# PWR_3V3.net
KiCad netlist of a schematic drawn in Altium Designer
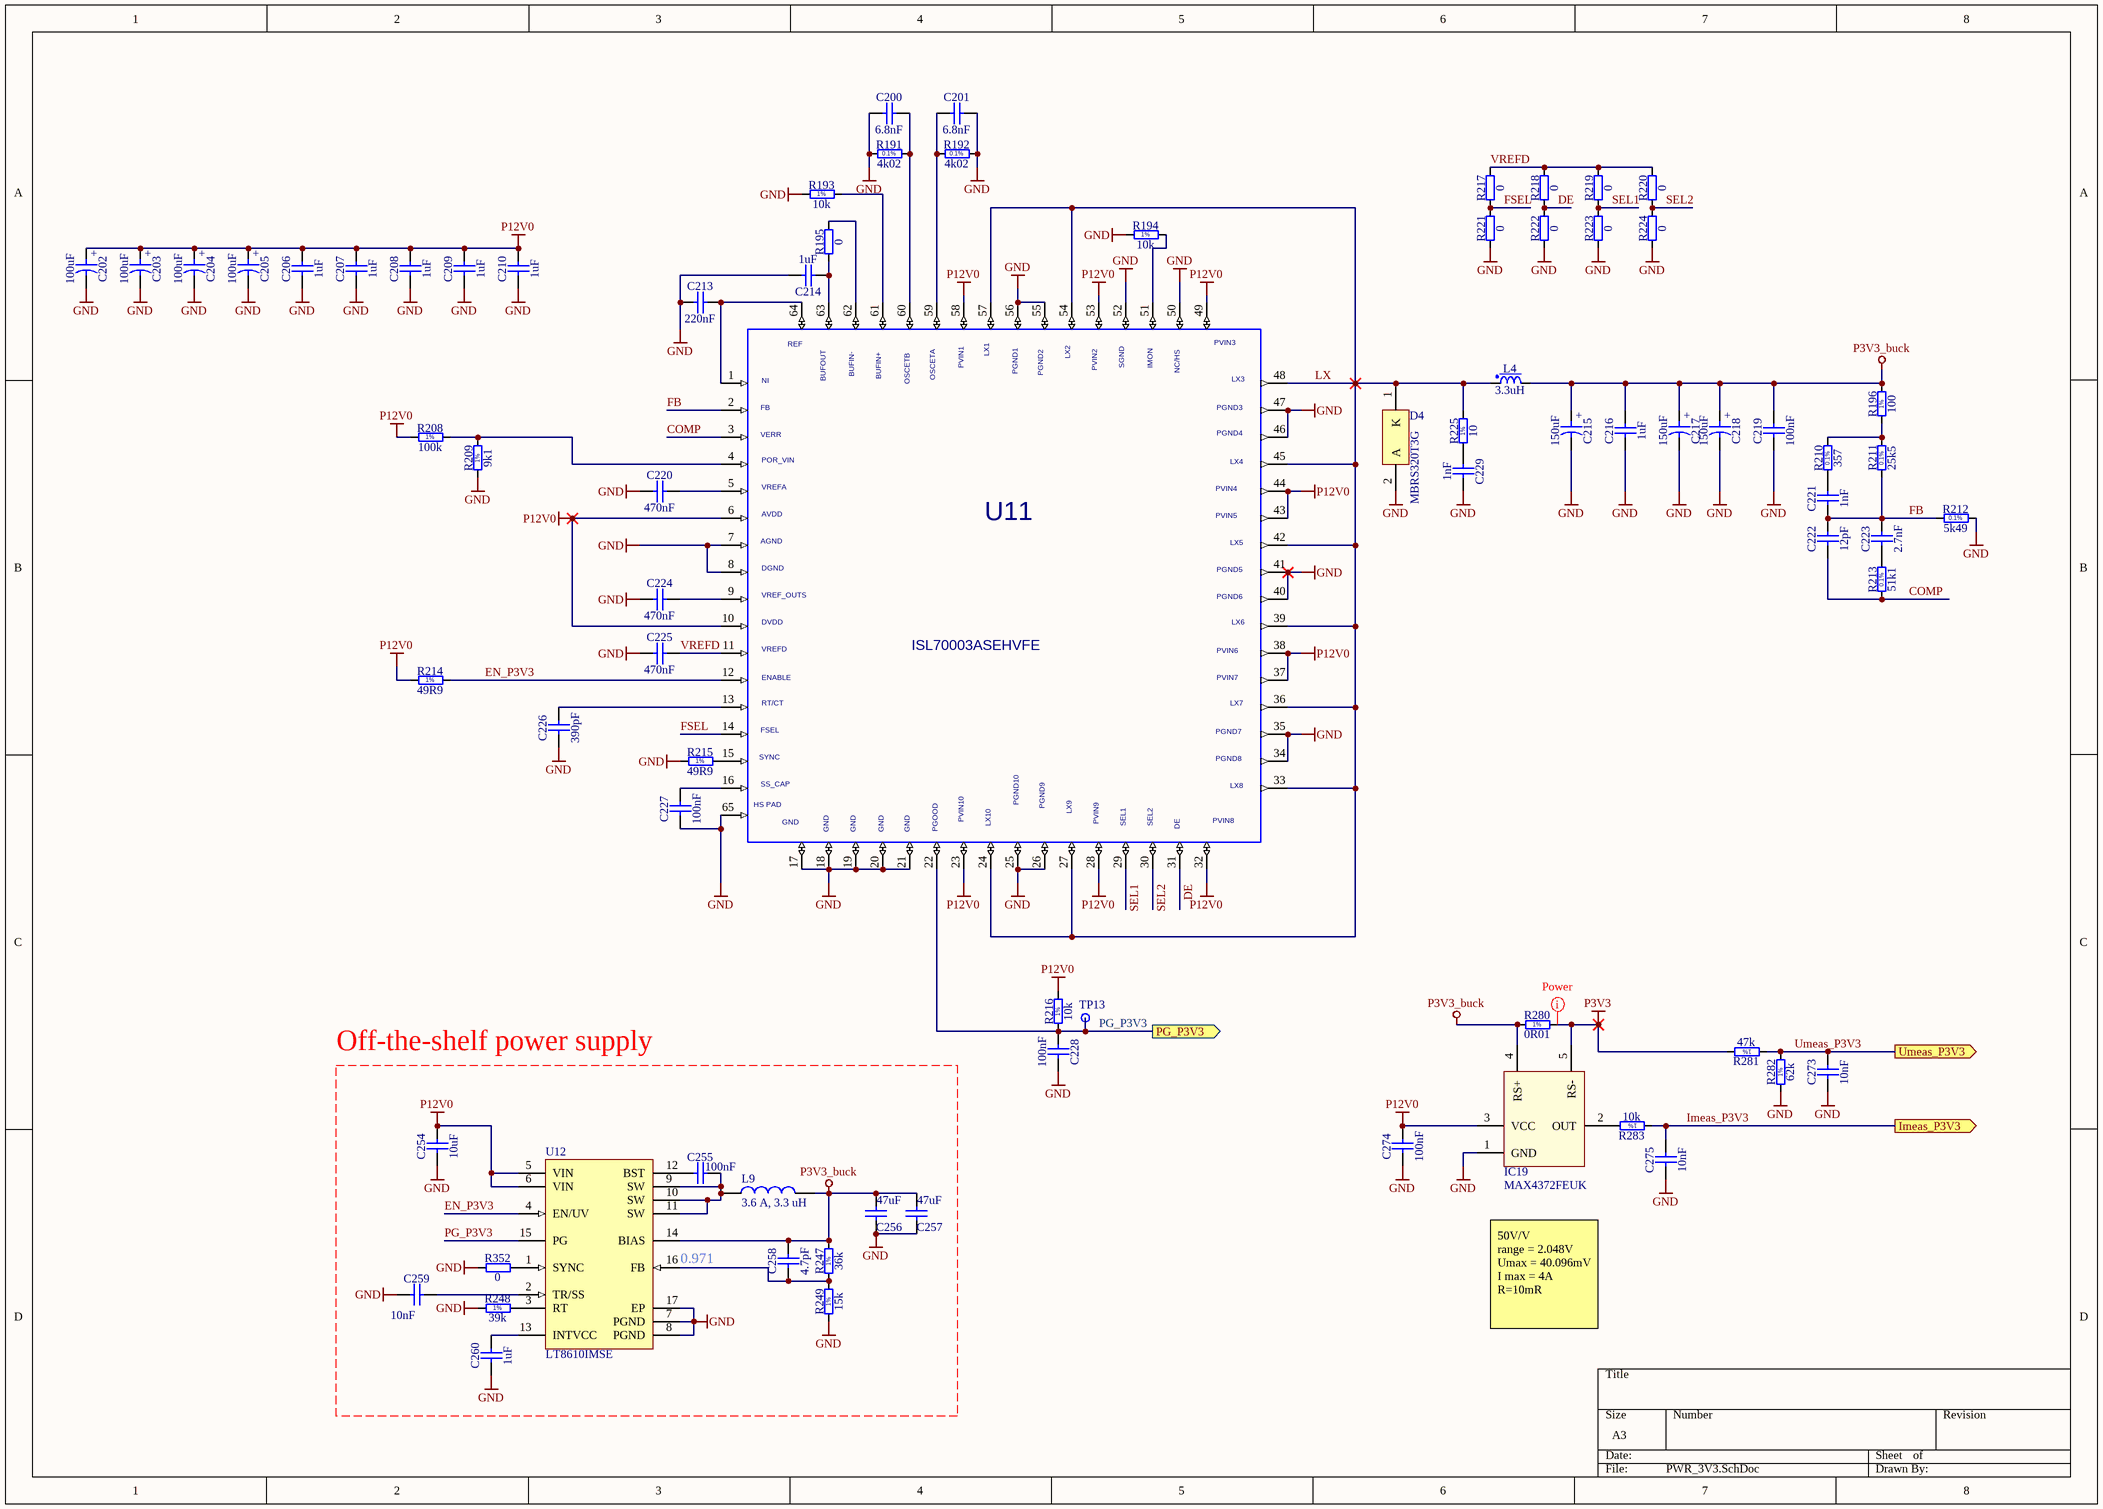
[diagram p0: PWR_3V3.SchDoc]

(export (version "E")
  (design (tool "Eeschema 10.0.6"))
  (components
    (comp (ref "C200")
      (value "6.8nF")
      (footprint "CAPC1005X55N")
      (description "Non-polarised capacitor")
      (fields
        (field (name "PART NUMBER") "CC0402_6.8NF_16V_10%_X7R")
        (field (name "VOLTAGE") "16V")
        (field (name "AUTHOR") "CERN DEM JLC")
      )
      (libsource (lib "Capacitors") (part "Capacitor - non polarized"))
    )
    (comp (ref "C201")
      (value "6.8nF")
      (footprint "CAPC1005X55N")
      (description "Non-polarised capacitor")
      (fields
        (field (name "PART NUMBER") "CC0402_6.8NF_16V_10%_X7R")
        (field (name "VOLTAGE") "16V")
        (field (name "AUTHOR") "CERN DEM JLC")
      )
      (libsource (lib "Capacitors") (part "Capacitor - non polarized"))
    )
    (comp (ref "C202")
      (value "100uF")
      (footprint "CAPMP7343X430N")
      (description "Polarised capacitor")
      (fields
        (field (name "PART NUMBER") "CTE7343-43_100UF_25V_10%_LESR0150")
        (field (name "VOLTAGE") "25V")
        (field (name "AUTHOR") "CERN DEM JLC")
      )
      (libsource (lib "Capacitors") (part "Capacitor - polarized"))
    )
    (comp (ref "C203")
      (value "100uF")
      (footprint "CAPMP7343X430N")
      (description "Polarised capacitor")
      (fields
        (field (name "PART NUMBER") "CTE7343-43_100UF_25V_10%_LESR0150")
        (field (name "VOLTAGE") "25V")
        (field (name "AUTHOR") "CERN DEM JLC")
      )
      (libsource (lib "Capacitors") (part "Capacitor - polarized"))
    )
    (comp (ref "C204")
      (value "100uF")
      (footprint "CAPMP7343X430N")
      (description "Polarised capacitor")
      (fields
        (field (name "PART NUMBER") "CTE7343-43_100UF_25V_10%_LESR0150")
        (field (name "VOLTAGE") "25V")
        (field (name "AUTHOR") "CERN DEM JLC")
      )
      (libsource (lib "Capacitors") (part "Capacitor - polarized"))
    )
    (comp (ref "C205")
      (value "100uF")
      (footprint "CAPMP7343X430N")
      (description "Polarised capacitor")
      (fields
        (field (name "PART NUMBER") "CTE7343-43_100UF_25V_10%_LESR0150")
        (field (name "VOLTAGE") "25V")
        (field (name "AUTHOR") "CERN DEM JLC")
      )
      (libsource (lib "Capacitors") (part "Capacitor - polarized"))
    )
    (comp (ref "C206")
      (value "1uF")
      (footprint "CAPC5650X165N")
      (description "Non-polarised capacitor")
      (fields
        (field (name "PART NUMBER") "CC2220_1UF_200V_10%_X7R")
        (field (name "VOLTAGE") "200V")
        (field (name "AUTHOR") "CERN DEM JLC")
      )
      (libsource (lib "Capacitors") (part "Capacitor - non polarized"))
    )
    (comp (ref "C207")
      (value "1uF")
      (footprint "CAPC5650X165N")
      (description "Non-polarised capacitor")
      (fields
        (field (name "PART NUMBER") "CC2220_1UF_200V_10%_X7R")
        (field (name "VOLTAGE") "200V")
        (field (name "AUTHOR") "CERN DEM JLC")
      )
      (libsource (lib "Capacitors") (part "Capacitor - non polarized"))
    )
    (comp (ref "C208")
      (value "1uF")
      (footprint "CAPC5650X165N")
      (description "Non-polarised capacitor")
      (fields
        (field (name "PART NUMBER") "CC2220_1UF_200V_10%_X7R")
        (field (name "VOLTAGE") "200V")
        (field (name "AUTHOR") "CERN DEM JLC")
      )
      (libsource (lib "Capacitors") (part "Capacitor - non polarized"))
    )
    (comp (ref "C209")
      (value "1uF")
      (footprint "CAPC5650X165N")
      (description "Non-polarised capacitor")
      (fields
        (field (name "PART NUMBER") "CC2220_1UF_200V_10%_X7R")
        (field (name "VOLTAGE") "200V")
        (field (name "AUTHOR") "CERN DEM JLC")
      )
      (libsource (lib "Capacitors") (part "Capacitor - non polarized"))
    )
    (comp (ref "C210")
      (value "1uF")
      (footprint "CAPC5650X165N")
      (description "Non-polarised capacitor")
      (fields
        (field (name "PART NUMBER") "CC2220_1UF_200V_10%_X7R")
        (field (name "VOLTAGE") "200V")
        (field (name "AUTHOR") "CERN DEM JLC")
      )
      (libsource (lib "Capacitors") (part "Capacitor - non polarized"))
    )
    (comp (ref "C213")
      (value "220nF")
      (footprint "CAPC1005X55N")
      (description "Non-polarised capacitor")
      (fields
        (field (name "PART NUMBER") "CC0402_220NF_16V_10%_X7R")
        (field (name "VOLTAGE") "16V")
        (field (name "AUTHOR") "CERN DEM JLC")
      )
      (libsource (lib "Capacitors") (part "Capacitor - non polarized"))
    )
    (comp (ref "C214")
      (value "1uF")
      (footprint "CAPC1005X55N")
      (description "Non-polarised capacitor")
      (fields
        (field (name "PART NUMBER") "CC0402_1UF_16V_10%_X5R")
        (field (name "VOLTAGE") "16V")
        (field (name "AUTHOR") "CERN DEM JLC")
      )
      (libsource (lib "Capacitors") (part "Capacitor - non polarized"))
    )
    (comp (ref "C215")
      (value "150uF")
      (footprint "CAPMP6032X280N")
      (description "Polarised capacitor")
      (fields
        (field (name "PART NUMBER") "CTE6032-28_150UF_10V_10%")
        (field (name "VOLTAGE") "10V")
        (field (name "AUTHOR") "CERN DEM JLC")
      )
      (libsource (lib "Capacitors") (part "Capacitor - polarized"))
    )
    (comp (ref "C216")
      (value "1uF")
      (footprint "CAPC5650X165N")
      (description "Non-polarised capacitor")
      (fields
        (field (name "PART NUMBER") "CC2220_1UF_200V_10%_X7R")
        (field (name "VOLTAGE") "200V")
        (field (name "AUTHOR") "CERN DEM JLC")
      )
      (libsource (lib "Capacitors") (part "Capacitor - non polarized"))
    )
    (comp (ref "C217")
      (value "150uF")
      (footprint "CAPMP6032X280N")
      (description "Polarised capacitor")
      (fields
        (field (name "PART NUMBER") "CTE6032-28_150UF_10V_10%")
        (field (name "VOLTAGE") "10V")
        (field (name "AUTHOR") "CERN DEM JLC")
      )
      (libsource (lib "Capacitors") (part "Capacitor - polarized"))
    )
    (comp (ref "C218")
      (value "150uF")
      (footprint "CAPMP6032X280N")
      (description "Polarised capacitor")
      (fields
        (field (name "PART NUMBER") "CTE6032-28_150UF_10V_10%")
        (field (name "VOLTAGE") "10V")
        (field (name "AUTHOR") "CERN DEM JLC")
      )
      (libsource (lib "Capacitors") (part "Capacitor - polarized"))
    )
    (comp (ref "C219")
      (value "100nF")
      (footprint "CAPC1608X87N")
      (description "Non-polarised capacitor")
      (fields
        (field (name "PART NUMBER") "CC0603_100NF_50V_10%_X5R")
        (field (name "VOLTAGE") "50V")
        (field (name "AUTHOR") "CERN DEM MR")
      )
      (libsource (lib "Capacitors") (part "Capacitor - non polarized"))
    )
    (comp (ref "C220")
      (value "470nF")
      (footprint "CAPC1005X55N")
      (description "Non-polarised capacitor")
      (fields
        (field (name "PART NUMBER") "CC0402_470NF_16V_10%_X5R")
        (field (name "VOLTAGE") "16V")
        (field (name "AUTHOR") "CERN DEM JLC")
      )
      (libsource (lib "Capacitors") (part "Capacitor - non polarized"))
    )
    (comp (ref "C221")
      (value "1nF")
      (footprint "CAPC1005X55N")
      (description "Non-polarised capacitor")
      (fields
        (field (name "PART NUMBER") "CC0402_1NF_50V_10%_X7R")
        (field (name "VOLTAGE") "50V")
        (field (name "AUTHOR") "CERN DEM JLC")
      )
      (libsource (lib "Capacitors") (part "Capacitor - non polarized"))
    )
    (comp (ref "C222")
      (value "12pF")
      (footprint "CAPC1005X55N")
      (description "Non-polarised capacitor")
      (fields
        (field (name "PART NUMBER") "CC0402_12PF_50V_5%_C0G")
        (field (name "VOLTAGE") "50V")
        (field (name "AUTHOR") "CERN DEM JLC")
      )
      (libsource (lib "Capacitors") (part "Capacitor - non polarized"))
    )
    (comp (ref "C223")
      (value "2.7nF")
      (footprint "CAPC1005X55N")
      (description "Non-polarised capacitor")
      (fields
        (field (name "PART NUMBER") "CC0402_2.7NF_50V_10%_X7R")
        (field (name "VOLTAGE") "50V")
        (field (name "AUTHOR") "CERN DEM JLC")
      )
      (libsource (lib "Capacitors") (part "Capacitor - non polarized"))
    )
    (comp (ref "C224")
      (value "470nF")
      (footprint "CAPC1005X55N")
      (description "Non-polarised capacitor")
      (fields
        (field (name "PART NUMBER") "CC0402_470NF_16V_10%_X5R")
        (field (name "VOLTAGE") "16V")
        (field (name "AUTHOR") "CERN DEM JLC")
      )
      (libsource (lib "Capacitors") (part "Capacitor - non polarized"))
    )
    (comp (ref "C225")
      (value "470nF")
      (footprint "CAPC1005X55N")
      (description "Non-polarised capacitor")
      (fields
        (field (name "PART NUMBER") "CC0402_470NF_16V_10%_X5R")
        (field (name "VOLTAGE") "16V")
        (field (name "AUTHOR") "CERN DEM JLC")
      )
      (libsource (lib "Capacitors") (part "Capacitor - non polarized"))
    )
    (comp (ref "C226")
      (value "390pF")
      (footprint "CAPC1608X87N")
      (description "Non-polarised capacitor")
      (fields
        (field (name "PART NUMBER") "CC0603_390PF_50V_5%_NP0")
        (field (name "VOLTAGE") "50V")
        (field (name "AUTHOR") "CERN DEM JLC")
      )
      (libsource (lib "Capacitors") (part "Capacitor - non polarized"))
    )
    (comp (ref "C227")
      (value "100nF")
      (footprint "CAPC1005X55N")
      (description "Non-polarised capacitor")
      (fields
        (field (name "PART NUMBER") "CC0402_100NF_16V_10%_X5R")
        (field (name "VOLTAGE") "16V")
        (field (name "AUTHOR") "CERN DEM JLC")
      )
      (libsource (lib "Capacitors") (part "Capacitor - non polarized"))
    )
    (comp (ref "C228")
      (value "100nF")
      (footprint "CAPC1005X55N")
      (description "Non-polarised capacitor")
      (fields
        (field (name "PART NUMBER") "CC0402_100NF_16V_10%_X5R")
        (field (name "VOLTAGE") "16V")
        (field (name "AUTHOR") "CERN DEM JLC")
      )
      (libsource (lib "Capacitors") (part "Capacitor - non polarized"))
    )
    (comp (ref "C229")
      (value "1nF")
      (footprint "CAPC1608X90N")
      (description "Non-polarised capacitor")
      (fields
        (field (name "PART NUMBER") "CC0603_1NF_50V_1%_NP0")
        (field (name "VOLTAGE") "50V")
        (field (name "AUTHOR") "CERN DEM JLC")
      )
      (libsource (lib "Capacitors") (part "Capacitor - non polarized"))
    )
    (comp (ref "C254")
      (value "10uF")
      (footprint "CAPC2012X95N")
      (description "Non-polarised capacitor")
      (fields
        (field (name "PART NUMBER") "CC0805_10UF_25V_10%_X5R")
        (field (name "VOLTAGE") "25V")
        (field (name "AUTHOR") "CERN DEM JLC")
      )
      (libsource (lib "Capacitors") (part "Capacitor - non polarized"))
    )
    (comp (ref "C255")
      (value "100nF")
      (footprint "CAPC1005X55N")
      (description "Non-polarised capacitor")
      (fields
        (field (name "PART NUMBER") "CC0402_100NF_25V_10%_X7R_YUDEN_TMK105B7104KVHF")
        (field (name "VOLTAGE") "25V")
        (field (name "AUTHOR") "CERN DEM JLC")
      )
      (libsource (lib "Capacitors") (part "Capacitor - non polarized"))
    )
    (comp (ref "C256")
      (value "47uF")
      (footprint "CAPC2012X140N")
      (description "Non-polarised capacitor")
      (fields
        (field (name "PART NUMBER") "CC0805_47UF_6.3V_20%_X5R")
        (field (name "MANUFACTURER") "GENERIC")
        (field (name "AUTHOR") "CERN DEM JLC")
      )
      (libsource (lib "Capacitors") (part "Capacitor - non polarized"))
    )
    (comp (ref "C257")
      (value "47uF")
      (footprint "CAPC2012X140N")
      (description "Non-polarised capacitor")
      (fields
        (field (name "PART NUMBER") "CC0805_47UF_6.3V_20%_X5R")
        (field (name "MANUFACTURER") "GENERIC")
        (field (name "AUTHOR") "CERN DEM JLC")
      )
      (libsource (lib "Capacitors") (part "Capacitor - non polarized"))
    )
    (comp (ref "C258")
      (value "4.7pF")
      (footprint "CAPC1005X55N")
      (description "Non-polarised capacitor")
      (fields
        (field (name "PART NUMBER") "CC0402_4.7PF_50V_0.25PF_C0G")
        (field (name "VOLTAGE") "50V")
        (field (name "AUTHOR") "CERN DEM JLC")
      )
      (libsource (lib "Capacitors") (part "Capacitor - non polarized"))
    )
    (comp (ref "C259")
      (value "10nF")
      (footprint "CAPC1005X55N")
      (description "Non-polarised capacitor")
      (fields
        (field (name "PART NUMBER") "CC0402_10NF_25V_10%_X7R")
        (field (name "VOLTAGE") "25V")
        (field (name "AUTHOR") "CERN DEM JLC")
      )
      (libsource (lib "Capacitors") (part "Capacitor - non polarized"))
    )
    (comp (ref "C260")
      (value "1uF")
      (footprint "CAPC1608X87N")
      (description "Non-polarised capacitor")
      (fields
        (field (name "PART NUMBER") "CC0603_1UF_25V_10%_X7R")
        (field (name "VOLTAGE") "25V")
        (field (name "AUTHOR") "CERN DEM JLC")
      )
      (libsource (lib "Capacitors") (part "Capacitor - non polarized"))
    )
    (comp (ref "C273")
      (value "10nF")
      (footprint "CAPC1005X55N")
      (description "Non-polarised capacitor")
      (fields
        (field (name "PART NUMBER") "CC0402_10NF_50V_10%_X7R")
        (field (name "VOLTAGE") "50V")
        (field (name "AUTHOR") "CERN DEM MR")
      )
      (libsource (lib "Capacitors") (part "Capacitor - non polarized"))
    )
    (comp (ref "C274")
      (value "100nF")
      (footprint "CAPC1005X55N")
      (description "Non-polarised capacitor")
      (fields
        (field (name "PART NUMBER") "CC0402_100NF_25V_10%_X7R_YUDEN_TMK105B7104KVHF")
        (field (name "VOLTAGE") "25V")
        (field (name "AUTHOR") "CERN DEM JLC")
      )
      (libsource (lib "Capacitors") (part "Capacitor - non polarized"))
    )
    (comp (ref "C275")
      (value "10nF")
      (footprint "CAPC1005X55N")
      (description "Non-polarised capacitor")
      (fields
        (field (name "PART NUMBER") "CC0402_10NF_50V_10%_X7R")
        (field (name "VOLTAGE") "50V")
        (field (name "AUTHOR") "CERN DEM MR")
      )
      (libsource (lib "Capacitors") (part "Capacitor - non polarized"))
    )
    (comp (ref "D4")
      (value "MBRS320T3G")
      (footprint "ONSC-SMC-2-403-03_V")
      (description "Schottky Power Rectifier, 2-Pin SMC, Pb-Free, Tape and Reel")
      (fields (field (name "MANUFACTURER") "On Semiconductor"))
      (libsource (lib "Altium Content Vault") (part "ONSC-D-K1A2-2_A"))
    )
    (comp (ref "IC19")
      (value "MAX4372FEUK")
      (footprint "SOT95P270X145-5N")
      (fields (field (name "MANUFACTURER") "Maxim"))
      (libsource (lib "LIBRARY_SCH") (part "PM_MAX4372FEUK"))
    )
    (comp (ref "L4")
      (value "3.3uH")
      (footprint "IND_LAIRD_MGV10043R3M-10")
      (description "Inductor With Magnetic core 1Dot")
      (fields
        (field (name "PART NUMBER") "IND_3.3UH_20%_LAIRD_MGV10043R3M-10")
        (field (name "POWER") "10A")
        (field (name "AUTHOR") "CERN DEM BC")
      )
      (libsource (lib "Inductors & Transformers") (part "Inductor With Magnetic core 1Dot"))
    )
    (comp (ref "L9")
      (value "3.6 A, 3.3 uH")
      (footprint "WE-MAIA_4020")
      (description "WE-MAIA SMD Power Inductor, size 4020, 3.6 A, 3.3 uH")
      (fields (field (name "PART NUMBER") "78438356033") (field (name "PUBLISHER") "Wurth Elektronik"))
      (libsource (lib "ALTIUM-WE-MAIA-rev17b") (part "78438356033"))
    )
    (comp (ref "R191")
      (value "4k02")
      (footprint "RESC1608X55N")
      (description "Resistor - 0.1%")
      (fields
        (field (name "PART NUMBER") "R0603_4K02_0.1%_0.063W_10PPM")
        (field (name "POWER") "0.063W")
        (field (name "AUTHOR") "CERN DEM JLC")
      )
      (libsource (lib "Resistors") (part "Resistor - 0.1%"))
    )
    (comp (ref "R192")
      (value "4k02")
      (footprint "RESC1608X55N")
      (description "Resistor - 0.1%")
      (fields
        (field (name "PART NUMBER") "R0603_4K02_0.1%_0.063W_10PPM")
        (field (name "POWER") "0.063W")
        (field (name "AUTHOR") "CERN DEM JLC")
      )
      (libsource (lib "Resistors") (part "Resistor - 0.1%"))
    )
    (comp (ref "R193")
      (value "10k")
      (footprint "RESC1005X40N")
      (description "Resistor - 1%")
      (fields
        (field (name "PART NUMBER") "R0402_10K_1%_0.0625W_100PPM")
        (field (name "POWER") "0.0625W")
        (field (name "AUTHOR") "CERN DEM JLC")
      )
      (libsource (lib "Resistors") (part "Resistor - 1%"))
    )
    (comp (ref "R194")
      (value "10k")
      (footprint "RESC1005X40N")
      (description "Resistor - 1%")
      (fields
        (field (name "PART NUMBER") "R0402_10K_1%_0.0625W_100PPM")
        (field (name "POWER") "0.0625W")
        (field (name "AUTHOR") "CERN DEM JLC")
      )
      (libsource (lib "Resistors") (part "Resistor - 1%"))
    )
    (comp (ref "R195")
      (value "0")
      (footprint "RESC1005X40N")
      (description "Resistor")
      (fields
        (field (name "PART NUMBER") "R0402_0R_JUMPER")
        (field (name "MANUFACTURER") "GENERIC")
        (field (name "AUTHOR") "CERN DEM JLC")
      )
      (libsource (lib "Resistors") (part "Resistor"))
    )
    (comp (ref "R196")
      (value "100")
      (footprint "RESC1005X40N")
      (description "Resistor - 1%")
      (fields
        (field (name "PART NUMBER") "R0402_100R_1%_0.0625W_100PPM")
        (field (name "POWER") "0.0625W")
        (field (name "AUTHOR") "CERN DEM JLC")
      )
      (libsource (lib "Resistors") (part "Resistor - 1%"))
    )
    (comp (ref "R208")
      (value "100k")
      (footprint "RESC1005X40N")
      (description "Resistor - 1%")
      (fields
        (field (name "PART NUMBER") "R0402_100K_1%_0.0625W_100PPM")
        (field (name "POWER") "0.0625W")
        (field (name "AUTHOR") "CERN DEM JLC")
      )
      (libsource (lib "Resistors") (part "Resistor - 1%"))
    )
    (comp (ref "R209")
      (value "9k1")
      (footprint "RESC1005X40N")
      (description "Resistor - 1%")
      (fields
        (field (name "PART NUMBER") "R0402_9K1_1%_0.0625W_100PPM")
        (field (name "POWER") "0.0625W")
        (field (name "AUTHOR") "CERN DEM JLC")
      )
      (libsource (lib "Resistors") (part "Resistor - 1%"))
    )
    (comp (ref "R210")
      (value "357")
      (footprint "RESC1608X55N")
      (description "Resistor - 0.1%")
      (fields
        (field (name "PART NUMBER") "R0603_357R_0.1%_0.063W_10PPM")
        (field (name "POWER") "0.063W")
        (field (name "AUTHOR") "CERN DEM JLC")
      )
      (libsource (lib "Resistors") (part "Resistor - 0.1%"))
    )
    (comp (ref "R211")
      (value "25k5")
      (footprint "RESC1608X55N")
      (description "Resistor - 0.1%")
      (fields
        (field (name "PART NUMBER") "R0603_25K5_0.1%_0.063W_10PPM")
        (field (name "POWER") "0.063W")
        (field (name "AUTHOR") "CERN DEM JLC")
      )
      (libsource (lib "Resistors") (part "Resistor - 0.1%"))
    )
    (comp (ref "R212")
      (value "5k49")
      (footprint "RESC1608X55N")
      (description "Resistor - 0.1%")
      (fields
        (field (name "PART NUMBER") "R0603_5K49_0.1%_0.063W_10PPM")
        (field (name "POWER") "0.063W")
        (field (name "AUTHOR") "CERN DEM JLC")
      )
      (libsource (lib "Resistors") (part "Resistor - 0.1%"))
    )
    (comp (ref "R213")
      (value "51k1")
      (footprint "RESC1608X55N")
      (description "Resistor - 0.1%")
      (fields
        (field (name "PART NUMBER") "R0603_51K1_0.1%_0.063W_10PPM")
        (field (name "POWER") "0.063W")
        (field (name "AUTHOR") "CERN DEM JLC")
      )
      (libsource (lib "Resistors") (part "Resistor - 0.1%"))
    )
    (comp (ref "R214")
      (value "49R9")
      (footprint "RESC1608X55N")
      (description "Resistor - 1%")
      (fields
        (field (name "PART NUMBER") "R0603_49K9_1%_0.1W_100PPM")
        (field (name "POWER") "0.1W")
        (field (name "AUTHOR") "CERN DEM JLC")
      )
      (libsource (lib "Resistors") (part "Resistor - 1%"))
    )
    (comp (ref "R215")
      (value "49R9")
      (footprint "RESC1005X40N")
      (description "Resistor - 1%")
      (fields
        (field (name "PART NUMBER") "R0402_49R9_1%_0.0625W_100PPM")
        (field (name "POWER") "0.0625W")
        (field (name "AUTHOR") "CERN DEM JLC")
      )
      (libsource (lib "Resistors") (part "Resistor - 1%"))
    )
    (comp (ref "R216")
      (value "10k")
      (footprint "RESC1005X40N")
      (description "Resistor - 1%")
      (fields
        (field (name "PART NUMBER") "R0402_10K_1%_0.0625W_100PPM")
        (field (name "POWER") "0.0625W")
        (field (name "AUTHOR") "CERN DEM JLC")
      )
      (libsource (lib "Resistors") (part "Resistor - 1%"))
    )
    (comp (ref "R217")
      (value "0")
      (footprint "RESC1005X40N")
      (description "Resistor")
      (fields
        (field (name "PART NUMBER") "R0402_0R_JUMPER")
        (field (name "MANUFACTURER") "GENERIC")
        (field (name "AUTHOR") "CERN DEM JLC")
      )
      (libsource (lib "Resistors") (part "Resistor"))
    )
    (comp (ref "R218")
      (value "0")
      (footprint "RESC1005X40N")
      (description "Resistor")
      (fields
        (field (name "PART NUMBER") "R0402_0R_JUMPER")
        (field (name "MANUFACTURER") "GENERIC")
        (field (name "AUTHOR") "CERN DEM JLC")
      )
      (libsource (lib "Resistors") (part "Resistor"))
    )
    (comp (ref "R219")
      (value "0")
      (footprint "RESC1005X40N")
      (description "Resistor")
      (fields
        (field (name "PART NUMBER") "R0402_0R_JUMPER")
        (field (name "MANUFACTURER") "GENERIC")
        (field (name "AUTHOR") "CERN DEM JLC")
      )
      (libsource (lib "Resistors") (part "Resistor"))
    )
    (comp (ref "R220")
      (value "0")
      (footprint "RESC1005X40N")
      (description "Resistor")
      (fields
        (field (name "PART NUMBER") "R0402_0R_JUMPER")
        (field (name "MANUFACTURER") "GENERIC")
        (field (name "AUTHOR") "CERN DEM JLC")
      )
      (libsource (lib "Resistors") (part "Resistor"))
    )
    (comp (ref "R221")
      (value "0")
      (footprint "RESC1005X40N")
      (description "Resistor")
      (fields
        (field (name "PART NUMBER") "R0402_0R_JUMPER")
        (field (name "MANUFACTURER") "GENERIC")
        (field (name "AUTHOR") "CERN DEM JLC")
      )
      (libsource (lib "Resistors") (part "Resistor"))
    )
    (comp (ref "R222")
      (value "0")
      (footprint "RESC1005X40N")
      (description "Resistor")
      (fields
        (field (name "PART NUMBER") "R0402_0R_JUMPER")
        (field (name "MANUFACTURER") "GENERIC")
        (field (name "AUTHOR") "CERN DEM JLC")
      )
      (libsource (lib "Resistors") (part "Resistor"))
    )
    (comp (ref "R223")
      (value "0")
      (footprint "RESC1005X40N")
      (description "Resistor")
      (fields
        (field (name "PART NUMBER") "R0402_0R_JUMPER")
        (field (name "MANUFACTURER") "GENERIC")
        (field (name "AUTHOR") "CERN DEM JLC")
      )
      (libsource (lib "Resistors") (part "Resistor"))
    )
    (comp (ref "R224")
      (value "0")
      (footprint "RESC1005X40N")
      (description "Resistor")
      (fields
        (field (name "PART NUMBER") "R0402_0R_JUMPER")
        (field (name "MANUFACTURER") "GENERIC")
        (field (name "AUTHOR") "CERN DEM JLC")
      )
      (libsource (lib "Resistors") (part "Resistor"))
    )
    (comp (ref "R225")
      (value "10")
      (footprint "RESC2012X60N")
      (description "Resistor - 1%")
      (fields
        (field (name "PART NUMBER") "R0805_10R_1%_0.125W_200PPM")
        (field (name "POWER") "0.125W")
        (field (name "AUTHOR") "CERN DEM JLC")
      )
      (libsource (lib "Resistors") (part "Resistor - 1%"))
    )
    (comp (ref "R247")
      (value "36k")
      (footprint "RESC1005X40N")
      (description "Resistor - 1%")
      (fields
        (field (name "PART NUMBER") "R0402_36K_1%_0.0625W_100PPM")
        (field (name "POWER") "0.0625W")
        (field (name "AUTHOR") "CERN DEM JLC")
      )
      (libsource (lib "Resistors") (part "Resistor - 1%"))
    )
    (comp (ref "R248")
      (value "39k")
      (footprint "RESC1005X40N")
      (description "Resistor - 1%")
      (fields
        (field (name "PART NUMBER") "R0402_39K_1%_0.0625W_100PPM")
        (field (name "POWER") "0.0625W")
        (field (name "AUTHOR") "CERN DEM JLC")
      )
      (libsource (lib "Resistors") (part "Resistor - 1%"))
    )
    (comp (ref "R249")
      (value "15k")
      (footprint "RESC1005X40N")
      (description "Resistor - 1%")
      (fields
        (field (name "PART NUMBER") "R0402_15K_1%_0.0625W_100PPM")
        (field (name "POWER") "0.0625W")
        (field (name "AUTHOR") "CERN DEM JMW")
      )
      (libsource (lib "Resistors") (part "Resistor - 1%"))
    )
    (comp (ref "R280")
      (value "0R01")
      (footprint "RESC3216X80N")
      (description "Resistor - 1%")
      (fields
        (field (name "PART NUMBER") "R1206_0R01_1%_1W_100PPM_TT_LRMAM1206")
        (field (name "POWER") "1W")
        (field (name "AUTHOR") "CERN DEM BC")
      )
      (libsource (lib "Resistors") (part "Resistor - 1%"))
    )
    (comp (ref "R281")
      (value "47k")
      (footprint "RESC1005X40N")
      (description "Resistor - 1%")
      (fields
        (field (name "PART NUMBER") "R0402_47K_1%_0.0625W_100PPM")
        (field (name "POWER") "0.0625W")
        (field (name "AUTHOR") "CERN DEM JLC")
      )
      (libsource (lib "Resistors") (part "Resistor - 1%"))
    )
    (comp (ref "R282")
      (value "62k")
      (footprint "RESC1005X40N")
      (description "Resistor - 1%")
      (fields
        (field (name "PART NUMBER") "R0402_62K_1%_0.0625W_100PPM")
        (field (name "POWER") "0.0625W")
        (field (name "AUTHOR") "CERN DEM JLC")
      )
      (libsource (lib "Resistors") (part "Resistor - 1%"))
    )
    (comp (ref "R283")
      (value "10k")
      (footprint "RESC1005X40N")
      (description "Resistor - 1%")
      (fields
        (field (name "PART NUMBER") "R0402_10K_1%_0.0625W_100PPM")
        (field (name "POWER") "0.0625W")
        (field (name "AUTHOR") "CERN DEM JLC")
      )
      (libsource (lib "Resistors") (part "Resistor - 1%"))
    )
    (comp (ref "R352")
      (value "0")
      (footprint "RESC1005X40N")
      (description "Resistor")
      (fields
        (field (name "PART NUMBER") "R0402_0R_JUMPER")
        (field (name "MANUFACTURER") "GENERIC")
        (field (name "AUTHOR") "CERN DEM JLC")
      )
      (libsource (lib "Resistors") (part "Resistor"))
    )
    (comp (ref "TP13")
      (value "Test Point")
      (footprint "TPS127")
      (fields (field (name "PART NUMBER") "SMD_PAD_1.27X1.27MM") (field (name "AUTHOR") "CERN DEM JLC"))
      (libsource (lib "Eletro-mechanical") (part "Test Point"))
    )
    (comp (ref "U11")
      (value "ISL70003ASEH")
      (footprint "CQFP64_555X555_635_EP")
      (fields (field (name "PART_NUMBER") "ISL70003ASEHVFE"))
      (libsource (lib "*") (part "ISL70003ASEH"))
    )
    (comp (ref "U12")
      (value "LT8610IMSE")
      (footprint "LT-MSE-16-EDP_L")
      (fields (field (name "MANUFACTURER") "Linear Technology"))
      (libsource (lib "Altium Content Vault") (part "LT-LT8610-MSE-16"))
    )
  )
  (nets
    (net (code "1") (name "/COMP") (class "Default")
      (node (ref "C222") (pin "1") (pinfunction "1_1") (pintype "passive"))
      (node (ref "R213") (pin "1") (pinfunction "1_1") (pintype "passive"))
      (node (ref "U11") (pin "3") (pinfunction "3_3") (pintype "input"))
    )
    (net (code "2") (name "/DE") (class "Default")
      (node (ref "R218") (pin "1") (pinfunction "1_1") (pintype "passive"))
      (node (ref "R222") (pin "2") (pinfunction "2_2") (pintype "passive"))
      (node (ref "U11") (pin "31") (pinfunction "31_31") (pintype "bidirectional"))
    )
    (net (code "3") (name "/EN_P3V3") (class "Default")
      (node (ref "R214") (pin "2") (pinfunction "2_2") (pintype "passive"))
      (node (ref "U11") (pin "12") (pinfunction "12_12") (pintype "input"))
      (node (ref "U12") (pin "4") (pinfunction "EN/UV_4") (pintype "input"))
    )
    (net (code "4") (name "/FB") (class "Default")
      (node (ref "C221") (pin "1") (pinfunction "1_1") (pintype "passive"))
      (node (ref "C222") (pin "2") (pinfunction "2_2") (pintype "passive"))
      (node (ref "C223") (pin "2") (pinfunction "2_2") (pintype "passive"))
      (node (ref "R211") (pin "1") (pinfunction "1_1") (pintype "passive"))
      (node (ref "R212") (pin "1") (pinfunction "1_1") (pintype "passive"))
      (node (ref "U11") (pin "2") (pinfunction "2_2") (pintype "input"))
    )
    (net (code "5") (name "/FSEL") (class "Default")
      (node (ref "R217") (pin "1") (pinfunction "1_1") (pintype "passive"))
      (node (ref "R221") (pin "2") (pinfunction "2_2") (pintype "passive"))
      (node (ref "U11") (pin "14") (pinfunction "14_14") (pintype "input"))
    )
    (net (code "6") (name "/Imeas_P3V3") (class "Default")
      (node (ref "C275") (pin "2") (pinfunction "2_2") (pintype "passive"))
      (node (ref "R283") (pin "1") (pinfunction "1_1") (pintype "passive"))
    )
    (net (code "7") (name "/LX") (class "Default")
      (node (ref "D4") (pin "1") (pinfunction "K_1") (pintype "passive"))
      (node (ref "L4") (pin "1") (pinfunction "1_1") (pintype "passive"))
      (node (ref "R225") (pin "2") (pinfunction "2_2") (pintype "passive"))
      (node (ref "U11") (pin "24") (pinfunction "24_24") (pintype "bidirectional"))
      (node (ref "U11") (pin "27") (pinfunction "27_27") (pintype "bidirectional"))
      (node (ref "U11") (pin "33") (pinfunction "33_33") (pintype "output"))
      (node (ref "U11") (pin "36") (pinfunction "36_36") (pintype "output"))
      (node (ref "U11") (pin "39") (pinfunction "39_39") (pintype "output"))
      (node (ref "U11") (pin "42") (pinfunction "42_42") (pintype "output"))
      (node (ref "U11") (pin "45") (pinfunction "45_45") (pintype "output"))
      (node (ref "U11") (pin "48") (pinfunction "48_48") (pintype "output"))
      (node (ref "U11") (pin "54") (pinfunction "54_54") (pintype "bidirectional"))
      (node (ref "U11") (pin "57") (pinfunction "57_57") (pintype "bidirectional"))
    )
    (net (code "8") (name "/PG_P3V3") (class "Default")
      (node (ref "C228") (pin "1") (pinfunction "1_1") (pintype "passive"))
      (node (ref "R216") (pin "1") (pinfunction "1_1") (pintype "passive"))
      (node (ref "TP13") (pin "1") (pinfunction "1_1") (pintype "bidirectional"))
      (node (ref "U11") (pin "22") (pinfunction "22_22") (pintype "bidirectional"))
      (node (ref "U12") (pin "15") (pinfunction "PG_15") (pintype "tri_state"))
    )
    (net (code "9") (name "/SEL1") (class "Default")
      (node (ref "R219") (pin "1") (pinfunction "1_1") (pintype "passive"))
      (node (ref "R223") (pin "2") (pinfunction "2_2") (pintype "passive"))
      (node (ref "U11") (pin "29") (pinfunction "29_29") (pintype "bidirectional"))
    )
    (net (code "10") (name "/SEL2") (class "Default")
      (node (ref "R220") (pin "1") (pinfunction "1_1") (pintype "passive"))
      (node (ref "R224") (pin "2") (pinfunction "2_2") (pintype "passive"))
      (node (ref "U11") (pin "30") (pinfunction "30_30") (pintype "bidirectional"))
    )
    (net (code "11") (name "/Umeas_P3V3") (class "Default")
      (node (ref "C273") (pin "2") (pinfunction "2_2") (pintype "passive"))
      (node (ref "R281") (pin "1") (pinfunction "1_1") (pintype "passive"))
      (node (ref "R282") (pin "2") (pinfunction "2_2") (pintype "passive"))
    )
    (net (code "12") (name "/VREFD") (class "Default")
      (node (ref "C225") (pin "2") (pinfunction "2_2") (pintype "passive"))
      (node (ref "R217") (pin "2") (pinfunction "2_2") (pintype "passive"))
      (node (ref "R218") (pin "2") (pinfunction "2_2") (pintype "passive"))
      (node (ref "R219") (pin "2") (pinfunction "2_2") (pintype "passive"))
      (node (ref "R220") (pin "2") (pinfunction "2_2") (pintype "passive"))
      (node (ref "U11") (pin "11") (pinfunction "11_11") (pintype "input"))
    )
    (net (code "13") (name "GND") (class "Default")
      (node (ref "C200") (pin "1") (pinfunction "1_1") (pintype "passive"))
      (node (ref "C201") (pin "2") (pinfunction "2_2") (pintype "passive"))
      (node (ref "C202") (pin "2") (pinfunction "2_2") (pintype "passive"))
      (node (ref "C203") (pin "2") (pinfunction "2_2") (pintype "passive"))
      (node (ref "C204") (pin "2") (pinfunction "2_2") (pintype "passive"))
      (node (ref "C205") (pin "2") (pinfunction "2_2") (pintype "passive"))
      (node (ref "C206") (pin "1") (pinfunction "1_1") (pintype "passive"))
      (node (ref "C207") (pin "1") (pinfunction "1_1") (pintype "passive"))
      (node (ref "C208") (pin "1") (pinfunction "1_1") (pintype "passive"))
      (node (ref "C209") (pin "1") (pinfunction "1_1") (pintype "passive"))
      (node (ref "C210") (pin "1") (pinfunction "1_1") (pintype "passive"))
      (node (ref "C213") (pin "1") (pinfunction "1_1") (pintype "passive"))
      (node (ref "C214") (pin "2") (pinfunction "2_2") (pintype "passive"))
      (node (ref "C215") (pin "2") (pinfunction "2_2") (pintype "passive"))
      (node (ref "C216") (pin "1") (pinfunction "1_1") (pintype "passive"))
      (node (ref "C217") (pin "2") (pinfunction "2_2") (pintype "passive"))
      (node (ref "C218") (pin "2") (pinfunction "2_2") (pintype "passive"))
      (node (ref "C219") (pin "1") (pinfunction "1_1") (pintype "passive"))
      (node (ref "C220") (pin "1") (pinfunction "1_1") (pintype "passive"))
      (node (ref "C224") (pin "1") (pinfunction "1_1") (pintype "passive"))
      (node (ref "C225") (pin "1") (pinfunction "1_1") (pintype "passive"))
      (node (ref "C226") (pin "1") (pinfunction "1_1") (pintype "passive"))
      (node (ref "C227") (pin "1") (pinfunction "1_1") (pintype "passive"))
      (node (ref "C228") (pin "2") (pinfunction "2_2") (pintype "passive"))
      (node (ref "C229") (pin "2") (pinfunction "2_2") (pintype "passive"))
      (node (ref "C254") (pin "1") (pinfunction "1_1") (pintype "passive"))
      (node (ref "C256") (pin "1") (pinfunction "1_1") (pintype "passive"))
      (node (ref "C257") (pin "1") (pinfunction "1_1") (pintype "passive"))
      (node (ref "C259") (pin "1") (pinfunction "1_1") (pintype "passive"))
      (node (ref "C260") (pin "1") (pinfunction "1_1") (pintype "passive"))
      (node (ref "C273") (pin "1") (pinfunction "1_1") (pintype "passive"))
      (node (ref "C274") (pin "1") (pinfunction "1_1") (pintype "passive"))
      (node (ref "C275") (pin "1") (pinfunction "1_1") (pintype "passive"))
      (node (ref "D4") (pin "2") (pinfunction "A_2") (pintype "passive"))
      (node (ref "IC19") (pin "1") (pinfunction "GND_1") (pintype "passive"))
      (node (ref "R191") (pin "1") (pinfunction "1_1") (pintype "passive"))
      (node (ref "R192") (pin "2") (pinfunction "2_2") (pintype "passive"))
      (node (ref "R193") (pin "1") (pinfunction "1_1") (pintype "passive"))
      (node (ref "R194") (pin "1") (pinfunction "1_1") (pintype "passive"))
      (node (ref "R209") (pin "1") (pinfunction "1_1") (pintype "passive"))
      (node (ref "R212") (pin "2") (pinfunction "2_2") (pintype "passive"))
      (node (ref "R215") (pin "1") (pinfunction "1_1") (pintype "passive"))
      (node (ref "R221") (pin "1") (pinfunction "1_1") (pintype "passive"))
      (node (ref "R222") (pin "1") (pinfunction "1_1") (pintype "passive"))
      (node (ref "R223") (pin "1") (pinfunction "1_1") (pintype "passive"))
      (node (ref "R224") (pin "1") (pinfunction "1_1") (pintype "passive"))
      (node (ref "R248") (pin "1") (pinfunction "1_1") (pintype "passive"))
      (node (ref "R249") (pin "1") (pinfunction "1_1") (pintype "passive"))
      (node (ref "R282") (pin "1") (pinfunction "1_1") (pintype "passive"))
      (node (ref "R352") (pin "1") (pinfunction "1_1") (pintype "passive"))
      (node (ref "U11") (pin "17") (pinfunction "17_17") (pintype "bidirectional"))
      (node (ref "U11") (pin "18") (pinfunction "18_18") (pintype "bidirectional"))
      (node (ref "U11") (pin "19") (pinfunction "19_19") (pintype "bidirectional"))
      (node (ref "U11") (pin "20") (pinfunction "20_20") (pintype "bidirectional"))
      (node (ref "U11") (pin "21") (pinfunction "21_21") (pintype "bidirectional"))
      (node (ref "U11") (pin "25") (pinfunction "25_25") (pintype "bidirectional"))
      (node (ref "U11") (pin "26") (pinfunction "26_26") (pintype "bidirectional"))
      (node (ref "U11") (pin "34") (pinfunction "34_34") (pintype "output"))
      (node (ref "U11") (pin "35") (pinfunction "35_35") (pintype "output"))
      (node (ref "U11") (pin "40") (pinfunction "40_40") (pintype "output"))
      (node (ref "U11") (pin "41") (pinfunction "41_41") (pintype "output"))
      (node (ref "U11") (pin "46") (pinfunction "46_46") (pintype "output"))
      (node (ref "U11") (pin "47") (pinfunction "47_47") (pintype "output"))
      (node (ref "U11") (pin "50") (pinfunction "50_50") (pintype "bidirectional"))
      (node (ref "U11") (pin "52") (pinfunction "52_52") (pintype "bidirectional"))
      (node (ref "U11") (pin "55") (pinfunction "55_55") (pintype "bidirectional"))
      (node (ref "U11") (pin "56") (pinfunction "56_56") (pintype "bidirectional"))
      (node (ref "U11") (pin "65") (pinfunction "EP_65") (pintype "input"))
      (node (ref "U11") (pin "7") (pinfunction "7_7") (pintype "input"))
      (node (ref "U11") (pin "8") (pinfunction "8_8") (pintype "input"))
      (node (ref "U12") (pin "17") (pinfunction "EP_17") (pintype "power_in"))
      (node (ref "U12") (pin "7") (pinfunction "PGND_7") (pintype "power_in"))
      (node (ref "U12") (pin "8") (pinfunction "PGND_8") (pintype "power_in"))
    )
    (net (code "14") (name "Net-(C200-Pad2)") (class "Default")
      (node (ref "C200") (pin "2") (pinfunction "2_2") (pintype "passive"))
      (node (ref "R191") (pin "2") (pinfunction "2_2") (pintype "passive"))
      (node (ref "U11") (pin "60") (pinfunction "60_60") (pintype "bidirectional"))
    )
    (net (code "15") (name "Net-(C201-Pad1)") (class "Default")
      (node (ref "C201") (pin "1") (pinfunction "1_1") (pintype "passive"))
      (node (ref "R192") (pin "1") (pinfunction "1_1") (pintype "passive"))
      (node (ref "U11") (pin "59") (pinfunction "59_59") (pintype "bidirectional"))
    )
    (net (code "16") (name "Net-(C213-Pad2)") (class "Default")
      (node (ref "C213") (pin "2") (pinfunction "2_2") (pintype "passive"))
      (node (ref "U11") (pin "1") (pinfunction "1_1") (pintype "input"))
      (node (ref "U11") (pin "64") (pinfunction "64_64") (pintype "bidirectional"))
    )
    (net (code "17") (name "Net-(C214-Pad1)") (class "Default")
      (node (ref "C214") (pin "1") (pinfunction "1_1") (pintype "passive"))
      (node (ref "R195") (pin "1") (pinfunction "1_1") (pintype "passive"))
      (node (ref "U11") (pin "63") (pinfunction "63_63") (pintype "bidirectional"))
    )
    (net (code "18") (name "Net-(C220-Pad2)") (class "Default")
      (node (ref "C220") (pin "2") (pinfunction "2_2") (pintype "passive"))
      (node (ref "U11") (pin "5") (pinfunction "5_5") (pintype "input"))
    )
    (net (code "19") (name "Net-(C221-Pad2)") (class "Default")
      (node (ref "C221") (pin "2") (pinfunction "2_2") (pintype "passive"))
      (node (ref "R210") (pin "1") (pinfunction "1_1") (pintype "passive"))
    )
    (net (code "20") (name "Net-(C223-Pad1)") (class "Default")
      (node (ref "C223") (pin "1") (pinfunction "1_1") (pintype "passive"))
      (node (ref "R213") (pin "2") (pinfunction "2_2") (pintype "passive"))
    )
    (net (code "21") (name "Net-(C224-Pad2)") (class "Default")
      (node (ref "C224") (pin "2") (pinfunction "2_2") (pintype "passive"))
      (node (ref "U11") (pin "9") (pinfunction "9_9") (pintype "input"))
    )
    (net (code "22") (name "Net-(C226-Pad2)") (class "Default")
      (node (ref "C226") (pin "2") (pinfunction "2_2") (pintype "passive"))
      (node (ref "U11") (pin "13") (pinfunction "13_13") (pintype "input"))
    )
    (net (code "23") (name "Net-(C227-Pad2)") (class "Default")
      (node (ref "C227") (pin "2") (pinfunction "2_2") (pintype "passive"))
      (node (ref "U11") (pin "16") (pinfunction "16_16") (pintype "input"))
    )
    (net (code "24") (name "Net-(C229-Pad1)") (class "Default")
      (node (ref "C229") (pin "1") (pinfunction "1_1") (pintype "passive"))
      (node (ref "R225") (pin "1") (pinfunction "1_1") (pintype "passive"))
    )
    (net (code "25") (name "Net-(C255-Pad2)") (class "Default")
      (node (ref "C255") (pin "2") (pinfunction "2_2") (pintype "passive"))
      (node (ref "L9") (pin "1") (pinfunction "1_1") (pintype "passive"))
      (node (ref "U12") (pin "10") (pinfunction "SW_10") (pintype "power_in"))
      (node (ref "U12") (pin "11") (pinfunction "SW_11") (pintype "power_in"))
      (node (ref "U12") (pin "9") (pinfunction "SW_9") (pintype "power_in"))
    )
    (net (code "26") (name "Net-(IC19-OUT)") (class "Default")
      (node (ref "IC19") (pin "2") (pinfunction "OUT_2") (pintype "passive"))
      (node (ref "R283") (pin "2") (pinfunction "2_2") (pintype "passive"))
    )
    (net (code "27") (name "Net-(R193-Pad2)") (class "Default")
      (node (ref "R193") (pin "2") (pinfunction "2_2") (pintype "passive"))
      (node (ref "U11") (pin "61") (pinfunction "61_61") (pintype "bidirectional"))
    )
    (net (code "28") (name "Net-(R194-Pad2)") (class "Default")
      (node (ref "R194") (pin "2") (pinfunction "2_2") (pintype "passive"))
      (node (ref "U11") (pin "51") (pinfunction "51_51") (pintype "bidirectional"))
    )
    (net (code "29") (name "Net-(R195-Pad2)") (class "Default")
      (node (ref "R195") (pin "2") (pinfunction "2_2") (pintype "passive"))
      (node (ref "U11") (pin "62") (pinfunction "62_62") (pintype "bidirectional"))
    )
    (net (code "30") (name "Net-(R196-Pad1)") (class "Default")
      (node (ref "R196") (pin "1") (pinfunction "1_1") (pintype "passive"))
      (node (ref "R210") (pin "2") (pinfunction "2_2") (pintype "passive"))
      (node (ref "R211") (pin "2") (pinfunction "2_2") (pintype "passive"))
    )
    (net (code "31") (name "Net-(R208-Pad2)") (class "Default")
      (node (ref "R208") (pin "2") (pinfunction "2_2") (pintype "passive"))
      (node (ref "R209") (pin "2") (pinfunction "2_2") (pintype "passive"))
      (node (ref "U11") (pin "4") (pinfunction "4_4") (pintype "input"))
    )
    (net (code "32") (name "Net-(R215-Pad2)") (class "Default")
      (node (ref "R215") (pin "2") (pinfunction "2_2") (pintype "passive"))
      (node (ref "U11") (pin "15") (pinfunction "15_15") (pintype "input"))
    )
    (net (code "33") (name "Net-(U12-BST)") (class "Default")
      (node (ref "C255") (pin "1") (pinfunction "1_1") (pintype "passive"))
      (node (ref "U12") (pin "12") (pinfunction "BST_12") (pintype "passive"))
    )
    (net (code "34") (name "Net-(U12-FB)") (class "Default")
      (node (ref "C258") (pin "1") (pinfunction "1_1") (pintype "passive"))
      (node (ref "R247") (pin "1") (pinfunction "1_1") (pintype "passive"))
      (node (ref "R249") (pin "2") (pinfunction "2_2") (pintype "passive"))
      (node (ref "U12") (pin "16") (pinfunction "FB_16") (pintype "input"))
    )
    (net (code "35") (name "Net-(U12-INTVCC)") (class "Default")
      (node (ref "C260") (pin "2") (pinfunction "2_2") (pintype "passive"))
      (node (ref "U12") (pin "13") (pinfunction "INTVCC_13") (pintype "power_in"))
    )
    (net (code "36") (name "Net-(U12-RT)") (class "Default")
      (node (ref "R248") (pin "2") (pinfunction "2_2") (pintype "passive"))
      (node (ref "U12") (pin "3") (pinfunction "RT_3") (pintype "passive"))
    )
    (net (code "37") (name "Net-(U12-SYNC)") (class "Default")
      (node (ref "R352") (pin "2") (pinfunction "2_2") (pintype "passive"))
      (node (ref "U12") (pin "1") (pinfunction "SYNC_1") (pintype "input"))
    )
    (net (code "38") (name "Net-(U12-TR{slash}SS)") (class "Default")
      (node (ref "C259") (pin "2") (pinfunction "2_2") (pintype "passive"))
      (node (ref "U12") (pin "2") (pinfunction "TR/SS_2") (pintype "input"))
    )
    (net (code "39") (name "P3V3") (class "Default")
      (node (ref "IC19") (pin "5") (pinfunction "RS-_5") (pintype "passive"))
      (node (ref "R280") (pin "2") (pinfunction "2_2") (pintype "passive"))
      (node (ref "R281") (pin "2") (pinfunction "2_2") (pintype "passive"))
    )
    (net (code "40") (name "P3V3_buck") (class "Default")
      (node (ref "C215") (pin "1") (pinfunction "1_1") (pintype "passive"))
      (node (ref "C216") (pin "2") (pinfunction "2_2") (pintype "passive"))
      (node (ref "C217") (pin "1") (pinfunction "1_1") (pintype "passive"))
      (node (ref "C218") (pin "1") (pinfunction "1_1") (pintype "passive"))
      (node (ref "C219") (pin "2") (pinfunction "2_2") (pintype "passive"))
      (node (ref "C256") (pin "2") (pinfunction "2_2") (pintype "passive"))
      (node (ref "C257") (pin "2") (pinfunction "2_2") (pintype "passive"))
      (node (ref "C258") (pin "2") (pinfunction "2_2") (pintype "passive"))
      (node (ref "IC19") (pin "4") (pinfunction "RS+_4") (pintype "passive"))
      (node (ref "L4") (pin "2") (pinfunction "2_2") (pintype "passive"))
      (node (ref "L9") (pin "2") (pinfunction "2_2") (pintype "passive"))
      (node (ref "R196") (pin "2") (pinfunction "2_2") (pintype "passive"))
      (node (ref "R247") (pin "2") (pinfunction "2_2") (pintype "passive"))
      (node (ref "R280") (pin "1") (pinfunction "1_1") (pintype "passive"))
      (node (ref "U12") (pin "14") (pinfunction "BIAS_14") (pintype "power_in"))
    )
    (net (code "41") (name "P12V0") (class "Default")
      (node (ref "C202") (pin "1") (pinfunction "1_1") (pintype "passive"))
      (node (ref "C203") (pin "1") (pinfunction "1_1") (pintype "passive"))
      (node (ref "C204") (pin "1") (pinfunction "1_1") (pintype "passive"))
      (node (ref "C205") (pin "1") (pinfunction "1_1") (pintype "passive"))
      (node (ref "C206") (pin "2") (pinfunction "2_2") (pintype "passive"))
      (node (ref "C207") (pin "2") (pinfunction "2_2") (pintype "passive"))
      (node (ref "C208") (pin "2") (pinfunction "2_2") (pintype "passive"))
      (node (ref "C209") (pin "2") (pinfunction "2_2") (pintype "passive"))
      (node (ref "C210") (pin "2") (pinfunction "2_2") (pintype "passive"))
      (node (ref "C254") (pin "2") (pinfunction "2_2") (pintype "passive"))
      (node (ref "C274") (pin "2") (pinfunction "2_2") (pintype "passive"))
      (node (ref "IC19") (pin "3") (pinfunction "VCC_3") (pintype "passive"))
      (node (ref "R208") (pin "1") (pinfunction "1_1") (pintype "passive"))
      (node (ref "R214") (pin "1") (pinfunction "1_1") (pintype "passive"))
      (node (ref "R216") (pin "2") (pinfunction "2_2") (pintype "passive"))
      (node (ref "U11") (pin "10") (pinfunction "10_10") (pintype "input"))
      (node (ref "U11") (pin "23") (pinfunction "23_23") (pintype "bidirectional"))
      (node (ref "U11") (pin "28") (pinfunction "28_28") (pintype "bidirectional"))
      (node (ref "U11") (pin "32") (pinfunction "32_32") (pintype "bidirectional"))
      (node (ref "U11") (pin "37") (pinfunction "37_37") (pintype "output"))
      (node (ref "U11") (pin "38") (pinfunction "38_38") (pintype "output"))
      (node (ref "U11") (pin "43") (pinfunction "43_43") (pintype "output"))
      (node (ref "U11") (pin "44") (pinfunction "44_44") (pintype "output"))
      (node (ref "U11") (pin "49") (pinfunction "49_49") (pintype "bidirectional"))
      (node (ref "U11") (pin "53") (pinfunction "53_53") (pintype "bidirectional"))
      (node (ref "U11") (pin "58") (pinfunction "58_58") (pintype "bidirectional"))
      (node (ref "U11") (pin "6") (pinfunction "6_6") (pintype "input"))
      (node (ref "U12") (pin "5") (pinfunction "VIN_5") (pintype "power_in"))
      (node (ref "U12") (pin "6") (pinfunction "VIN_6") (pintype "power_in"))
    )
  )
)
